# BTN_1_1.net
KiCad netlist of a schematic drawn in EAGLE
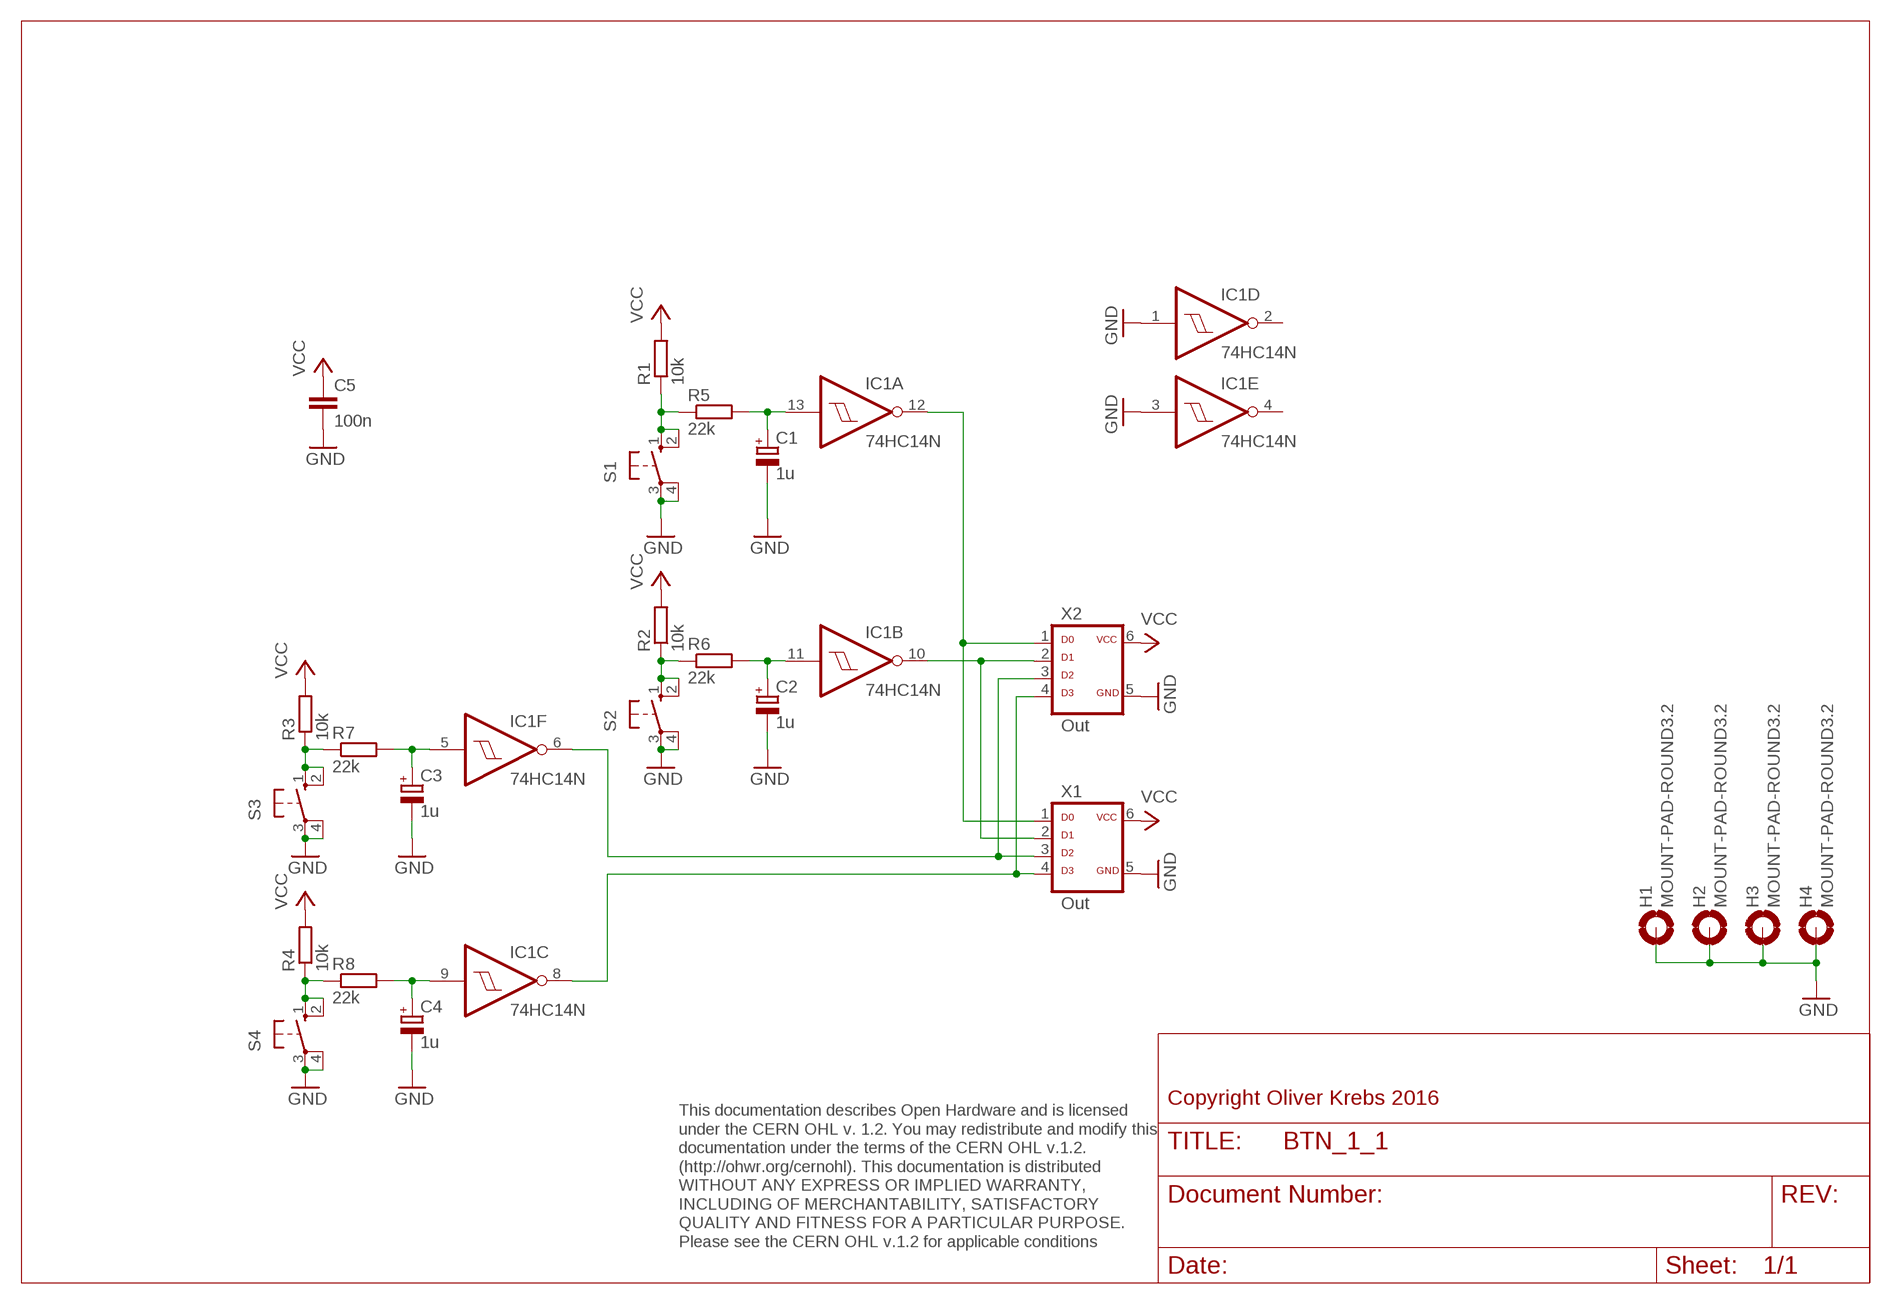
[diagram p0: schematic, sheet 1]

(export (version "E")
  (design (tool "Eeschema 10.0.6"))
  (components
    (comp (ref "C1")
      (value "1u")
      (footprint "eagle-import:E2-5")
      (libsource (lib "eagle-import") (part "CPOL-EUE2-5"))
    )
    (comp (ref "C2")
      (value "1u")
      (footprint "eagle-import:E2-5")
      (libsource (lib "eagle-import") (part "CPOL-EUE2-5"))
    )
    (comp (ref "C3")
      (value "1u")
      (footprint "eagle-import:E2-5")
      (libsource (lib "eagle-import") (part "CPOL-EUE2-5"))
    )
    (comp (ref "C4")
      (value "1u")
      (footprint "eagle-import:E2-5")
      (libsource (lib "eagle-import") (part "CPOL-EUE2-5"))
    )
    (comp (ref "C5")
      (value "100n")
      (footprint "eagle-import:C050-025X075")
      (libsource (lib "eagle-import") (part "C-EU050-025X075"))
    )
    (comp (ref "H1")
      (value "MOUNT-PAD-ROUND3.2")
      (footprint "eagle-import:3,2-PAD")
      (libsource (lib "eagle-import") (part "MOUNT-PAD-ROUND3.2"))
    )
    (comp (ref "H2")
      (value "MOUNT-PAD-ROUND3.2")
      (footprint "eagle-import:3,2-PAD")
      (libsource (lib "eagle-import") (part "MOUNT-PAD-ROUND3.2"))
    )
    (comp (ref "H3")
      (value "MOUNT-PAD-ROUND3.2")
      (footprint "eagle-import:3,2-PAD")
      (libsource (lib "eagle-import") (part "MOUNT-PAD-ROUND3.2"))
    )
    (comp (ref "H4")
      (value "MOUNT-PAD-ROUND3.2")
      (footprint "eagle-import:3,2-PAD")
      (libsource (lib "eagle-import") (part "MOUNT-PAD-ROUND3.2"))
    )
    (comp (ref "IC1")
      (value "74HC14N")
      (footprint "eagle-import:DIL14")
      (libsource (lib "eagle-import") (part "7414NHC"))
    )
    (comp (ref "R1")
      (value "10k")
      (footprint "eagle-import:0207_10")
      (libsource (lib "eagle-import") (part "R-EU_0207/10"))
    )
    (comp (ref "R2")
      (value "10k")
      (footprint "eagle-import:0207_10")
      (libsource (lib "eagle-import") (part "R-EU_0207/10"))
    )
    (comp (ref "R3")
      (value "10k")
      (footprint "eagle-import:0207_10")
      (libsource (lib "eagle-import") (part "R-EU_0207/10"))
    )
    (comp (ref "R4")
      (value "10k")
      (footprint "eagle-import:0207_10")
      (libsource (lib "eagle-import") (part "R-EU_0207/10"))
    )
    (comp (ref "R5")
      (value "22k")
      (footprint "eagle-import:0207_10")
      (libsource (lib "eagle-import") (part "R-EU_0207/10"))
    )
    (comp (ref "R6")
      (value "22k")
      (footprint "eagle-import:0207_10")
      (libsource (lib "eagle-import") (part "R-EU_0207/10"))
    )
    (comp (ref "R7")
      (value "22k")
      (footprint "eagle-import:0207_10")
      (libsource (lib "eagle-import") (part "R-EU_0207/10"))
    )
    (comp (ref "R8")
      (value "22k")
      (footprint "eagle-import:0207_10")
      (libsource (lib "eagle-import") (part "R-EU_0207/10"))
    )
    (comp (ref "S1")
      (value "10-XX")
      (footprint "eagle-import:B3F-10XX")
      (fields (field (name "MPN") "B3F-1000"))
      (libsource (lib "eagle-import") (part "10-XX"))
    )
    (comp (ref "S2")
      (value "10-XX")
      (footprint "eagle-import:B3F-10XX")
      (fields (field (name "MPN") "B3F-1000"))
      (libsource (lib "eagle-import") (part "10-XX"))
    )
    (comp (ref "S3")
      (value "10-XX")
      (footprint "eagle-import:B3F-10XX")
      (fields (field (name "MPN") "B3F-1000"))
      (libsource (lib "eagle-import") (part "10-XX"))
    )
    (comp (ref "S4")
      (value "10-XX")
      (footprint "eagle-import:B3F-10XX")
      (fields (field (name "MPN") "B3F-1000"))
      (libsource (lib "eagle-import") (part "10-XX"))
    )
    (comp (ref "X1")
      (value "Out")
      (footprint "eagle-import:ML-6")
      (libsource (lib "eagle-import") (part "ML6D"))
    )
    (comp (ref "X2")
      (value "Out")
      (footprint "eagle-import:ML-6")
      (libsource (lib "eagle-import") (part "ML6D"))
    )
  )
  (nets
    (net (code "1") (name "GND") (class "Default")
      (node (ref "C1") (pin "-") (pinfunction "-_-") (pintype "passive"))
      (node (ref "C2") (pin "-") (pinfunction "-_-") (pintype "passive"))
      (node (ref "C3") (pin "-") (pinfunction "-_-") (pintype "passive"))
      (node (ref "C4") (pin "-") (pinfunction "-_-") (pintype "passive"))
      (node (ref "C5") (pin "2") (pinfunction "2_2") (pintype "passive"))
      (node (ref "H1") (pin "B3,2") (pinfunction "MOUNT_B3,2") (pintype "passive"))
      (node (ref "H2") (pin "B3,2") (pinfunction "MOUNT_B3,2") (pintype "passive"))
      (node (ref "H3") (pin "B3,2") (pinfunction "MOUNT_B3,2") (pintype "passive"))
      (node (ref "H4") (pin "B3,2") (pinfunction "MOUNT_B3,2") (pintype "passive"))
      (node (ref "IC1") (pin "1") (pinfunction "I_1") (pintype "input"))
      (node (ref "IC1") (pin "3") (pinfunction "I_3") (pintype "input"))
      (node (ref "S1") (pin "3") (pinfunction "P_3") (pintype "passive"))
      (node (ref "S1") (pin "4") (pinfunction "P1_4") (pintype "passive"))
      (node (ref "S2") (pin "3") (pinfunction "P_3") (pintype "passive"))
      (node (ref "S2") (pin "4") (pinfunction "P1_4") (pintype "passive"))
      (node (ref "S3") (pin "3") (pinfunction "P_3") (pintype "passive"))
      (node (ref "S3") (pin "4") (pinfunction "P1_4") (pintype "passive"))
      (node (ref "S4") (pin "3") (pinfunction "P_3") (pintype "passive"))
      (node (ref "S4") (pin "4") (pinfunction "P1_4") (pintype "passive"))
      (node (ref "X1") (pin "5") (pinfunction "5_5") (pintype "passive"))
      (node (ref "X2") (pin "5") (pinfunction "5_5") (pintype "passive"))
    )
    (net (code "2") (name "Net-(IC1A-I)") (class "Default")
      (node (ref "C1") (pin "+") (pinfunction "+_+") (pintype "passive"))
      (node (ref "IC1") (pin "13") (pinfunction "I_13") (pintype "input"))
      (node (ref "R5") (pin "2") (pinfunction "2_2") (pintype "passive"))
    )
    (net (code "3") (name "Net-(IC1A-O)") (class "Default")
      (node (ref "IC1") (pin "12") (pinfunction "O_12") (pintype "output"))
      (node (ref "X1") (pin "1") (pinfunction "1_1") (pintype "passive"))
      (node (ref "X2") (pin "1") (pinfunction "1_1") (pintype "passive"))
    )
    (net (code "4") (name "Net-(IC1B-I)") (class "Default")
      (node (ref "C2") (pin "+") (pinfunction "+_+") (pintype "passive"))
      (node (ref "IC1") (pin "11") (pinfunction "I_11") (pintype "input"))
      (node (ref "R6") (pin "2") (pinfunction "2_2") (pintype "passive"))
    )
    (net (code "5") (name "Net-(IC1B-O)") (class "Default")
      (node (ref "IC1") (pin "10") (pinfunction "O_10") (pintype "output"))
      (node (ref "X1") (pin "2") (pinfunction "2_2") (pintype "passive"))
      (node (ref "X2") (pin "2") (pinfunction "2_2") (pintype "passive"))
    )
    (net (code "6") (name "Net-(IC1C-I)") (class "Default")
      (node (ref "C4") (pin "+") (pinfunction "+_+") (pintype "passive"))
      (node (ref "IC1") (pin "9") (pinfunction "I_9") (pintype "input"))
      (node (ref "R8") (pin "2") (pinfunction "2_2") (pintype "passive"))
    )
    (net (code "7") (name "Net-(IC1C-O)") (class "Default")
      (node (ref "IC1") (pin "8") (pinfunction "O_8") (pintype "output"))
      (node (ref "X1") (pin "4") (pinfunction "4_4") (pintype "passive"))
      (node (ref "X2") (pin "4") (pinfunction "4_4") (pintype "passive"))
    )
    (net (code "8") (name "Net-(IC1F-I)") (class "Default")
      (node (ref "C3") (pin "+") (pinfunction "+_+") (pintype "passive"))
      (node (ref "IC1") (pin "5") (pinfunction "I_5") (pintype "input"))
      (node (ref "R7") (pin "2") (pinfunction "2_2") (pintype "passive"))
    )
    (net (code "9") (name "Net-(IC1F-O)") (class "Default")
      (node (ref "IC1") (pin "6") (pinfunction "O_6") (pintype "output"))
      (node (ref "X1") (pin "3") (pinfunction "3_3") (pintype "passive"))
      (node (ref "X2") (pin "3") (pinfunction "3_3") (pintype "passive"))
    )
    (net (code "10") (name "Net-(S1-S)") (class "Default")
      (node (ref "R1") (pin "1") (pinfunction "1_1") (pintype "passive"))
      (node (ref "R5") (pin "1") (pinfunction "1_1") (pintype "passive"))
      (node (ref "S1") (pin "1") (pinfunction "S_1") (pintype "passive"))
      (node (ref "S1") (pin "2") (pinfunction "S1_2") (pintype "passive"))
    )
    (net (code "11") (name "Net-(S2-S)") (class "Default")
      (node (ref "R2") (pin "1") (pinfunction "1_1") (pintype "passive"))
      (node (ref "R6") (pin "1") (pinfunction "1_1") (pintype "passive"))
      (node (ref "S2") (pin "1") (pinfunction "S_1") (pintype "passive"))
      (node (ref "S2") (pin "2") (pinfunction "S1_2") (pintype "passive"))
    )
    (net (code "12") (name "Net-(S3-S)") (class "Default")
      (node (ref "R3") (pin "1") (pinfunction "1_1") (pintype "passive"))
      (node (ref "R7") (pin "1") (pinfunction "1_1") (pintype "passive"))
      (node (ref "S3") (pin "1") (pinfunction "S_1") (pintype "passive"))
      (node (ref "S3") (pin "2") (pinfunction "S1_2") (pintype "passive"))
    )
    (net (code "13") (name "Net-(S4-S)") (class "Default")
      (node (ref "R4") (pin "1") (pinfunction "1_1") (pintype "passive"))
      (node (ref "R8") (pin "1") (pinfunction "1_1") (pintype "passive"))
      (node (ref "S4") (pin "1") (pinfunction "S_1") (pintype "passive"))
      (node (ref "S4") (pin "2") (pinfunction "S1_2") (pintype "passive"))
    )
    (net (code "14") (name "VCC") (class "Default")
      (node (ref "C5") (pin "1") (pinfunction "1_1") (pintype "passive"))
      (node (ref "R1") (pin "2") (pinfunction "2_2") (pintype "passive"))
      (node (ref "R2") (pin "2") (pinfunction "2_2") (pintype "passive"))
      (node (ref "R3") (pin "2") (pinfunction "2_2") (pintype "passive"))
      (node (ref "R4") (pin "2") (pinfunction "2_2") (pintype "passive"))
      (node (ref "X1") (pin "6") (pinfunction "6_6") (pintype "passive"))
      (node (ref "X2") (pin "6") (pinfunction "6_6") (pintype "passive"))
    )
    (net (code "15") (name "unconnected-(IC1D-O-Pad2)") (class "Default")
      (node (ref "IC1") (pin "2") (pinfunction "O_2") (pintype "output"))
    )
    (net (code "16") (name "unconnected-(IC1E-O-Pad4)") (class "Default")
      (node (ref "IC1") (pin "4") (pinfunction "O_4") (pintype "output"))
    )
  )
)
